# voltage_doubler.net
KiCad netlist of a schematic drawn in EAGLE
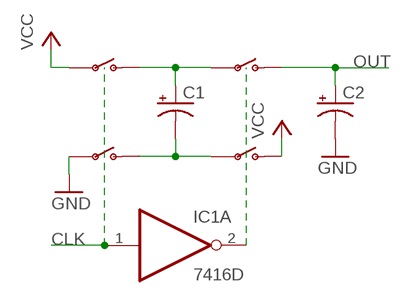
[diagram p0: schematic, sheet 1]

(export (version "E")
  (design (tool "Eeschema 10.0.6"))
  (components
    (comp (ref "C1")
      (value "CAP_POL1206")
      (footprint "eagle-import:EIA3216")
      (libsource (lib "eagle-import") (part "CAP_POL1206"))
    )
    (comp (ref "C2")
      (value "CAP_POL1206")
      (footprint "eagle-import:EIA3216")
      (libsource (lib "eagle-import") (part "CAP_POL1206"))
    )
    (comp (ref "IC1")
      (value "7416D")
      (footprint "eagle-import:SO14")
      (libsource (lib "eagle-import") (part "7416D"))
    )
    (comp (ref "U$1")
      (value "SWITCH-SPST-2RA")
      (footprint "eagle-import:R_SW_TH")
      (libsource (lib "eagle-import") (part "SWITCH-SPST-2RA"))
    )
    (comp (ref "U$2")
      (value "SWITCH-SPST-2RA")
      (footprint "eagle-import:R_SW_TH")
      (libsource (lib "eagle-import") (part "SWITCH-SPST-2RA"))
    )
    (comp (ref "U$3")
      (value "SWITCH-SPST-2RA")
      (footprint "eagle-import:R_SW_TH")
      (libsource (lib "eagle-import") (part "SWITCH-SPST-2RA"))
    )
    (comp (ref "U$4")
      (value "SWITCH-SPST-2RA")
      (footprint "eagle-import:R_SW_TH")
      (libsource (lib "eagle-import") (part "SWITCH-SPST-2RA"))
    )
  )
  (nets
    (net (code "1") (name "/CLK") (class "Default")
      (node (ref "IC1") (pin "1") (pinfunction "I_1") (pintype "input"))
    )
    (net (code "2") (name "/OUT") (class "Default")
      (node (ref "C2") (pin "A") (pinfunction "+_A") (pintype "passive"))
      (node (ref "U$2") (pin "P$3") (pinfunction "O_P$3") (pintype "passive"))
    )
    (net (code "3") (name "GND") (class "Default")
      (node (ref "C2") (pin "C") (pinfunction "-_C") (pintype "passive"))
      (node (ref "U$3") (pin "P$4") (pinfunction "P_P$4") (pintype "passive"))
    )
    (net (code "4") (name "Net-(C1-+)") (class "Default")
      (node (ref "C1") (pin "A") (pinfunction "+_A") (pintype "passive"))
      (node (ref "U$1") (pin "P$3") (pinfunction "O_P$3") (pintype "passive"))
      (node (ref "U$2") (pin "P$4") (pinfunction "P_P$4") (pintype "passive"))
    )
    (net (code "5") (name "Net-(C1--)") (class "Default")
      (node (ref "C1") (pin "C") (pinfunction "-_C") (pintype "passive"))
      (node (ref "U$3") (pin "P$3") (pinfunction "O_P$3") (pintype "passive"))
      (node (ref "U$4") (pin "P$4") (pinfunction "P_P$4") (pintype "passive"))
    )
    (net (code "6") (name "VCC") (class "Default")
      (node (ref "U$1") (pin "P$4") (pinfunction "P_P$4") (pintype "passive"))
      (node (ref "U$4") (pin "P$3") (pinfunction "O_P$3") (pintype "passive"))
    )
    (net (code "7") (name "unconnected-(IC1A-O-Pad2)") (class "Default")
      (node (ref "IC1") (pin "2") (pinfunction "O_2") (pintype "open_collector"))
    )
  )
)
